# Adafruit_MCP9601.net
KiCad netlist of a schematic drawn in EAGLE
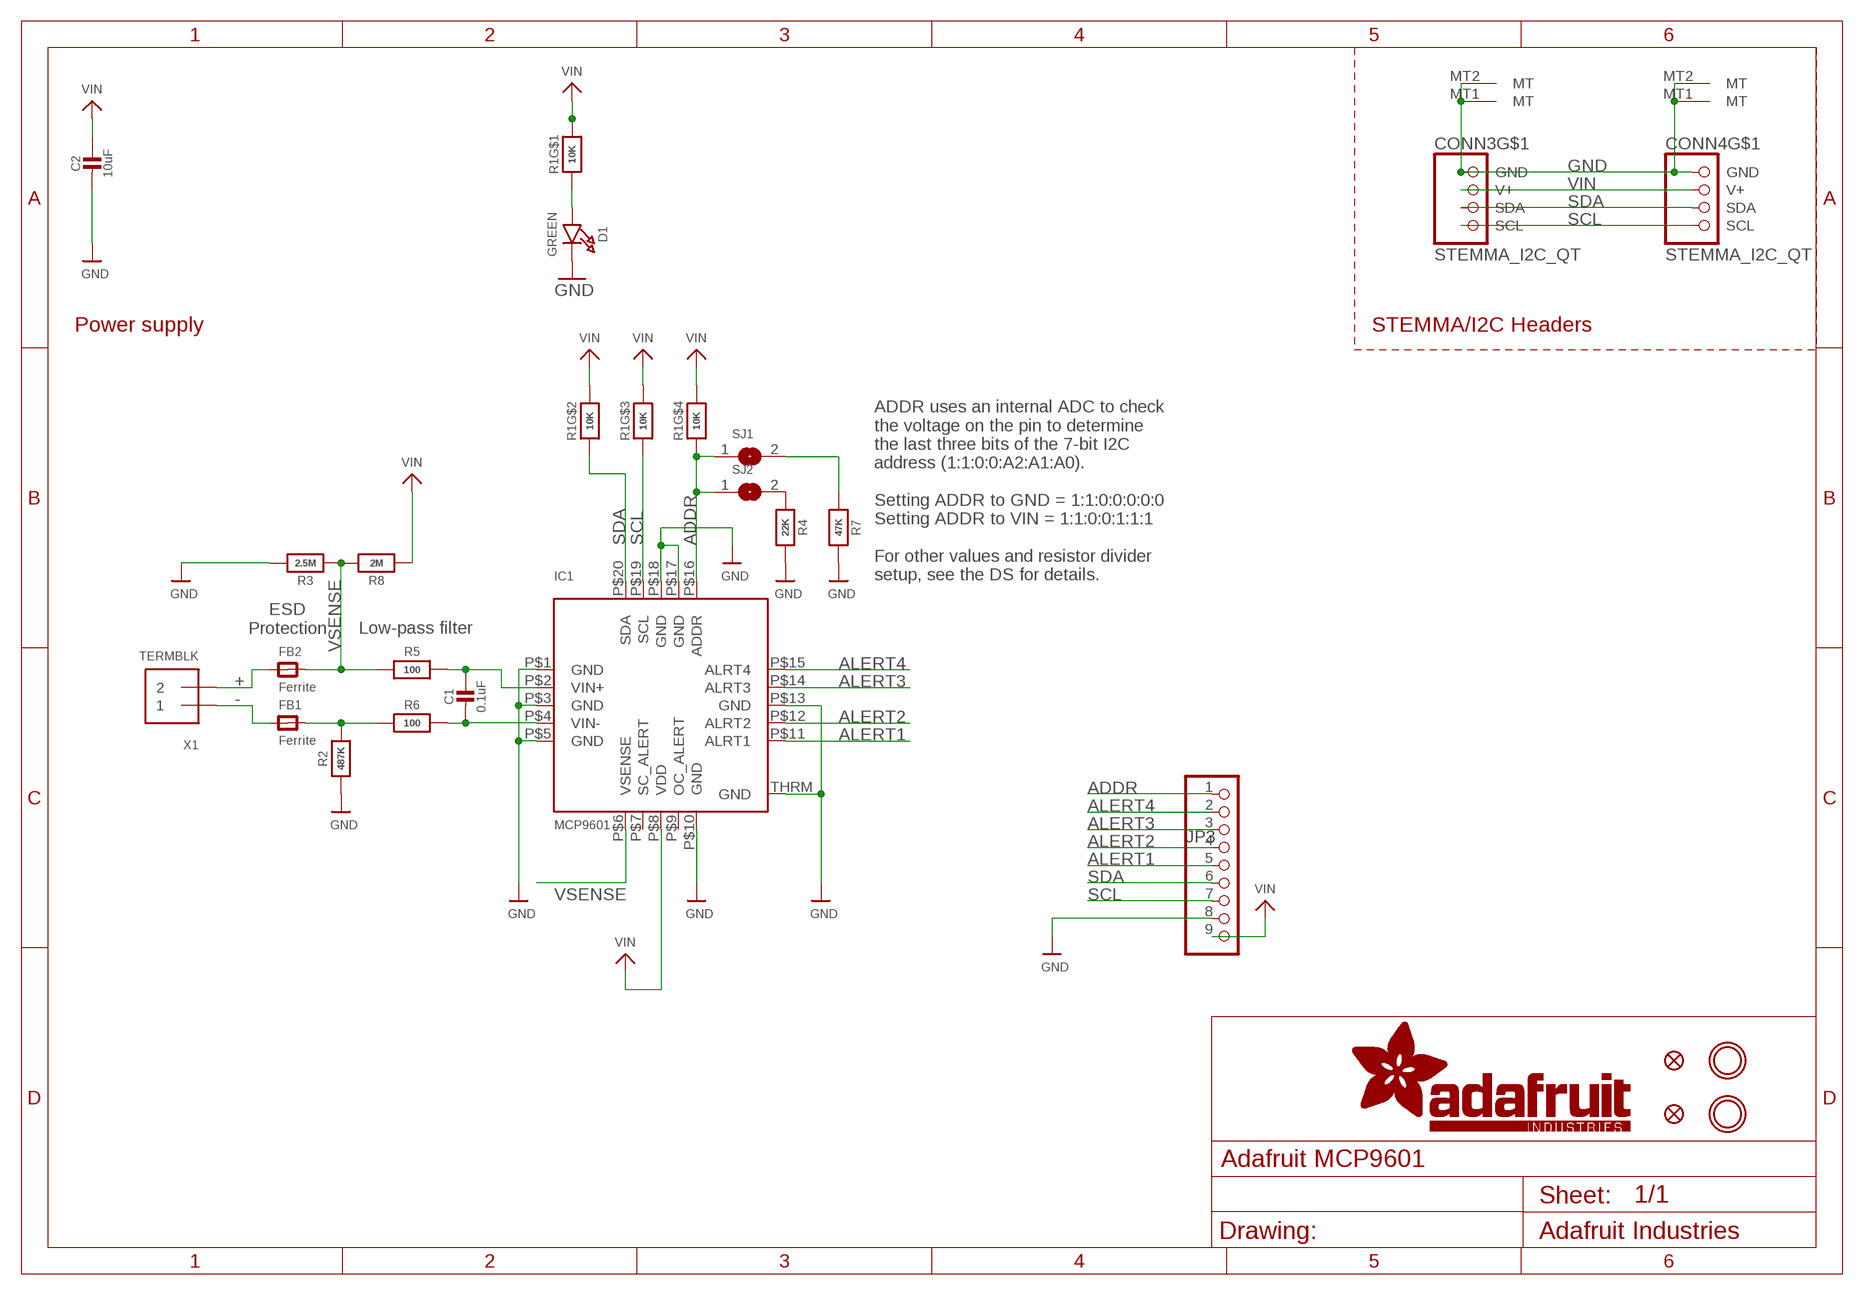
[diagram p0: schematic, sheet 1]

(export (version "E")
  (design (tool "Eeschema 10.0.6"))
  (components
    (comp (ref "C1")
      (value "0.1uF")
      (footprint "eagle-import:0603-NO")
      (libsource (lib "eagle-import") (part "CAP_CERAMIC0603_NO"))
    )
    (comp (ref "C2")
      (value "10uF")
      (footprint "eagle-import:0805-NO")
      (libsource (lib "eagle-import") (part "CAP_CERAMIC0805-NOOUTLINE"))
    )
    (comp (ref "CONN3")
      (value "STEMMA_I2C_QT")
      (footprint "eagle-import:JST_SH4")
      (libsource (lib "eagle-import") (part "STEMMA_I2C_QT"))
    )
    (comp (ref "CONN4")
      (value "STEMMA_I2C_QT")
      (footprint "eagle-import:JST_SH4")
      (libsource (lib "eagle-import") (part "STEMMA_I2C_QT"))
    )
    (comp (ref "D1")
      (value "GREEN")
      (footprint "eagle-import:CHIPLED_0603_NOOUTLINE")
      (libsource (lib "eagle-import") (part "LED0603_NOOUTLINE"))
    )
    (comp (ref "FB1")
      (value "Ferrite")
      (footprint "eagle-import:0603-NO")
      (libsource (lib "eagle-import") (part "FERRITE-0603NO"))
    )
    (comp (ref "FB2")
      (value "Ferrite")
      (footprint "eagle-import:0603-NO")
      (libsource (lib "eagle-import") (part "FERRITE-0603NO"))
    )
    (comp (ref "FID3")
      (value "FIDUCIAL_1MM")
      (footprint "eagle-import:FIDUCIAL_1MM")
      (libsource (lib "eagle-import") (part "FIDUCIAL_1MM"))
    )
    (comp (ref "FID4")
      (value "FIDUCIAL_1MM")
      (footprint "eagle-import:FIDUCIAL_1MM")
      (libsource (lib "eagle-import") (part "FIDUCIAL_1MM"))
    )
    (comp (ref "IC1")
      (value "MCP9601")
      (footprint "eagle-import:VQFN20_5MM")
      (libsource (lib "eagle-import") (part "MCP9601"))
    )
    (comp (ref "JP3")
      (value "HEADER-1X970MIL")
      (footprint "eagle-import:1X09_ROUND_70")
      (libsource (lib "eagle-import") (part "HEADER-1X970MIL"))
    )
    (comp (ref "R1")
      (value "10K")
      (footprint "eagle-import:RESPACK_4X0603")
      (libsource (lib "eagle-import") (part "RESISTOR_4PACK"))
    )
    (comp (ref "R2")
      (value "487K")
      (footprint "eagle-import:0603-NO")
      (libsource (lib "eagle-import") (part "RESISTOR_0603_NOOUT"))
    )
    (comp (ref "R3")
      (value "2.5M")
      (footprint "eagle-import:0603-NO")
      (libsource (lib "eagle-import") (part "RESISTOR_0603_NOOUT"))
    )
    (comp (ref "R4")
      (value "22K")
      (footprint "eagle-import:0603-NO")
      (libsource (lib "eagle-import") (part "RESISTOR_0603_NOOUT"))
    )
    (comp (ref "R5")
      (value "100")
      (footprint "eagle-import:0603-NO")
      (libsource (lib "eagle-import") (part "RESISTOR_0603_NOOUT"))
    )
    (comp (ref "R6")
      (value "100")
      (footprint "eagle-import:0603-NO")
      (libsource (lib "eagle-import") (part "RESISTOR_0603_NOOUT"))
    )
    (comp (ref "R7")
      (value "47K")
      (footprint "eagle-import:0603-NO")
      (libsource (lib "eagle-import") (part "RESISTOR_0603_NOOUT"))
    )
    (comp (ref "R8")
      (value "2M")
      (footprint "eagle-import:0603-NO")
      (libsource (lib "eagle-import") (part "RESISTOR_0603_NOOUT"))
    )
    (comp (ref "SJ1")
      (value "SOLDERJUMPER")
      (footprint "eagle-import:SOLDERJUMPER_ARROW_NOPASTE")
      (libsource (lib "eagle-import") (part "SOLDERJUMPER"))
    )
    (comp (ref "SJ2")
      (value "SOLDERJUMPER")
      (footprint "eagle-import:SOLDERJUMPER_ARROW_NOPASTE")
      (libsource (lib "eagle-import") (part "SOLDERJUMPER"))
    )
    (comp (ref "U$33")
      (value "MOUNTINGHOLE2.5")
      (footprint "eagle-import:MOUNTINGHOLE_2.5_PLATED")
      (libsource (lib "eagle-import") (part "MOUNTINGHOLE2.5"))
    )
    (comp (ref "U$34")
      (value "MOUNTINGHOLE2.5")
      (footprint "eagle-import:MOUNTINGHOLE_2.5_PLATED")
      (libsource (lib "eagle-import") (part "MOUNTINGHOLE2.5"))
    )
    (comp (ref "X1")
      (value "TERMBLK")
      (footprint "eagle-import:TERMBLOCK_1X2-3.5MM")
      (libsource (lib "eagle-import") (part "TERMBLOCK_1X2_3.5MM"))
    )
  )
  (nets
    (net (code "1") (name "/+") (class "Default")
      (node (ref "FB2") (pin "1") (pinfunction "P$1_1") (pintype "passive"))
      (node (ref "X1") (pin "2") (pinfunction "2_2") (pintype "passive"))
    )
    (net (code "2") (name "/-") (class "Default")
      (node (ref "FB1") (pin "1") (pinfunction "P$1_1") (pintype "passive"))
      (node (ref "X1") (pin "1") (pinfunction "1_1") (pintype "passive"))
    )
    (net (code "3") (name "/ADDR") (class "Default")
      (node (ref "IC1") (pin "P$16") (pinfunction "ADDR_P$16") (pintype "bidirectional"))
      (node (ref "JP3") (pin "1") (pinfunction "1_1") (pintype "passive"))
      (node (ref "R1") (pin "4") (pinfunction "1_4") (pintype "passive"))
      (node (ref "SJ1") (pin "1") (pinfunction "1_1") (pintype "passive"))
      (node (ref "SJ2") (pin "1") (pinfunction "1_1") (pintype "passive"))
    )
    (net (code "4") (name "/ALERT1") (class "Default")
      (node (ref "IC1") (pin "P$11") (pinfunction "ALRT1_P$11") (pintype "bidirectional"))
      (node (ref "JP3") (pin "5") (pinfunction "5_5") (pintype "passive"))
    )
    (net (code "5") (name "/ALERT2") (class "Default")
      (node (ref "IC1") (pin "P$12") (pinfunction "ALRT2_P$12") (pintype "bidirectional"))
      (node (ref "JP3") (pin "4") (pinfunction "4_4") (pintype "passive"))
    )
    (net (code "6") (name "/ALERT3") (class "Default")
      (node (ref "IC1") (pin "P$14") (pinfunction "ALRT3_P$14") (pintype "bidirectional"))
      (node (ref "JP3") (pin "3") (pinfunction "3_3") (pintype "passive"))
    )
    (net (code "7") (name "/ALERT4") (class "Default")
      (node (ref "IC1") (pin "P$15") (pinfunction "ALRT4_P$15") (pintype "bidirectional"))
      (node (ref "JP3") (pin "2") (pinfunction "2_2") (pintype "passive"))
    )
    (net (code "8") (name "/SCL") (class "Default")
      (node (ref "CONN3") (pin "4") (pinfunction "SCL_4") (pintype "passive"))
      (node (ref "CONN4") (pin "4") (pinfunction "SCL_4") (pintype "passive"))
      (node (ref "IC1") (pin "P$19") (pinfunction "SCL_P$19") (pintype "bidirectional"))
      (node (ref "JP3") (pin "7") (pinfunction "7_7") (pintype "passive"))
      (node (ref "R1") (pin "3") (pinfunction "1_3") (pintype "passive"))
    )
    (net (code "9") (name "/SDA") (class "Default")
      (node (ref "CONN3") (pin "3") (pinfunction "SDA_3") (pintype "passive"))
      (node (ref "CONN4") (pin "3") (pinfunction "SDA_3") (pintype "passive"))
      (node (ref "IC1") (pin "P$20") (pinfunction "SDA_P$20") (pintype "bidirectional"))
      (node (ref "JP3") (pin "6") (pinfunction "6_6") (pintype "passive"))
      (node (ref "R1") (pin "2") (pinfunction "1_2") (pintype "passive"))
    )
    (net (code "10") (name "/VSENSE") (class "Default")
      (node (ref "FB2") (pin "2") (pinfunction "P$2_2") (pintype "passive"))
      (node (ref "IC1") (pin "P$6") (pinfunction "VSENSE_P$6") (pintype "bidirectional"))
      (node (ref "R3") (pin "1") (pinfunction "1_1") (pintype "passive"))
      (node (ref "R5") (pin "1") (pinfunction "1_1") (pintype "passive"))
      (node (ref "R8") (pin "2") (pinfunction "2_2") (pintype "passive"))
    )
    (net (code "11") (name "GND") (class "Default")
      (node (ref "C2") (pin "2") (pinfunction "2_2") (pintype "passive"))
      (node (ref "CONN3") (pin "1") (pinfunction "GND_1") (pintype "passive"))
      (node (ref "CONN3") (pin "MT1") (pinfunction "MT_MT1") (pintype "bidirectional"))
      (node (ref "CONN3") (pin "MT2") (pinfunction "MT_MT2") (pintype "bidirectional"))
      (node (ref "CONN4") (pin "1") (pinfunction "GND_1") (pintype "passive"))
      (node (ref "CONN4") (pin "MT1") (pinfunction "MT_MT1") (pintype "bidirectional"))
      (node (ref "CONN4") (pin "MT2") (pinfunction "MT_MT2") (pintype "bidirectional"))
      (node (ref "D1") (pin "C") (pinfunction "C_C") (pintype "passive"))
      (node (ref "IC1") (pin "P$1") (pinfunction "GND_P$1") (pintype "bidirectional"))
      (node (ref "IC1") (pin "P$10") (pinfunction "GND_P$10") (pintype "bidirectional"))
      (node (ref "IC1") (pin "P$13") (pinfunction "GND_P$13") (pintype "bidirectional"))
      (node (ref "IC1") (pin "P$17") (pinfunction "GND_P$17") (pintype "bidirectional"))
      (node (ref "IC1") (pin "P$18") (pinfunction "GND_P$18") (pintype "bidirectional"))
      (node (ref "IC1") (pin "P$3") (pinfunction "GND_P$3") (pintype "bidirectional"))
      (node (ref "IC1") (pin "P$5") (pinfunction "GND_P$5") (pintype "bidirectional"))
      (node (ref "IC1") (pin "THRM") (pinfunction "GND_THRM") (pintype "bidirectional"))
      (node (ref "JP3") (pin "8") (pinfunction "8_8") (pintype "passive"))
      (node (ref "R2") (pin "1") (pinfunction "1_1") (pintype "passive"))
      (node (ref "R3") (pin "2") (pinfunction "2_2") (pintype "passive"))
      (node (ref "R4") (pin "2") (pinfunction "2_2") (pintype "passive"))
      (node (ref "R7") (pin "2") (pinfunction "2_2") (pintype "passive"))
    )
    (net (code "12") (name "Net-(D1-PadA)") (class "Default")
      (node (ref "D1") (pin "A") (pinfunction "A_A") (pintype "passive"))
      (node (ref "R1") (pin "1") (pinfunction "1_1") (pintype "passive"))
    )
    (net (code "13") (name "Net-(FB1-P$2)") (class "Default")
      (node (ref "FB1") (pin "2") (pinfunction "P$2_2") (pintype "passive"))
      (node (ref "R2") (pin "2") (pinfunction "2_2") (pintype "passive"))
      (node (ref "R6") (pin "1") (pinfunction "1_1") (pintype "passive"))
    )
    (net (code "14") (name "Net-(IC1-VIN+)") (class "Default")
      (node (ref "C1") (pin "1") (pinfunction "1_1") (pintype "passive"))
      (node (ref "IC1") (pin "P$2") (pinfunction "VIN+_P$2") (pintype "bidirectional"))
      (node (ref "R5") (pin "2") (pinfunction "2_2") (pintype "passive"))
    )
    (net (code "15") (name "Net-(IC1-VIN-)") (class "Default")
      (node (ref "C1") (pin "2") (pinfunction "2_2") (pintype "passive"))
      (node (ref "IC1") (pin "P$4") (pinfunction "VIN-_P$4") (pintype "bidirectional"))
      (node (ref "R6") (pin "2") (pinfunction "2_2") (pintype "passive"))
    )
    (net (code "16") (name "Net-(R4-Pad1)") (class "Default")
      (node (ref "R4") (pin "1") (pinfunction "1_1") (pintype "passive"))
      (node (ref "SJ2") (pin "2") (pinfunction "2_2") (pintype "passive"))
    )
    (net (code "17") (name "Net-(R7-Pad1)") (class "Default")
      (node (ref "R7") (pin "1") (pinfunction "1_1") (pintype "passive"))
      (node (ref "SJ1") (pin "2") (pinfunction "2_2") (pintype "passive"))
    )
    (net (code "18") (name "VIN") (class "Default")
      (node (ref "C2") (pin "1") (pinfunction "1_1") (pintype "passive"))
      (node (ref "CONN3") (pin "2") (pinfunction "V+_2") (pintype "passive"))
      (node (ref "CONN4") (pin "2") (pinfunction "V+_2") (pintype "passive"))
      (node (ref "IC1") (pin "P$8") (pinfunction "VDD_P$8") (pintype "bidirectional"))
      (node (ref "JP3") (pin "9") (pinfunction "9_9") (pintype "passive"))
      (node (ref "R1") (pin "5") (pinfunction "2_5") (pintype "passive"))
      (node (ref "R1") (pin "6") (pinfunction "2_6") (pintype "passive"))
      (node (ref "R1") (pin "7") (pinfunction "2_7") (pintype "passive"))
      (node (ref "R1") (pin "8") (pinfunction "2_8") (pintype "passive"))
      (node (ref "R8") (pin "1") (pinfunction "1_1") (pintype "passive"))
    )
    (net (code "19") (name "unconnected-(IC1-OC_ALERT-PadP$9)") (class "Default")
      (node (ref "IC1") (pin "P$9") (pinfunction "OC_ALERT_P$9") (pintype "output"))
    )
    (net (code "20") (name "unconnected-(IC1-SC_ALERT-PadP$7)") (class "Default")
      (node (ref "IC1") (pin "P$7") (pinfunction "SC_ALERT_P$7") (pintype "output"))
    )
  )
)
